# water_buzzer.net
KiCad netlist of a schematic drawn in EAGLE
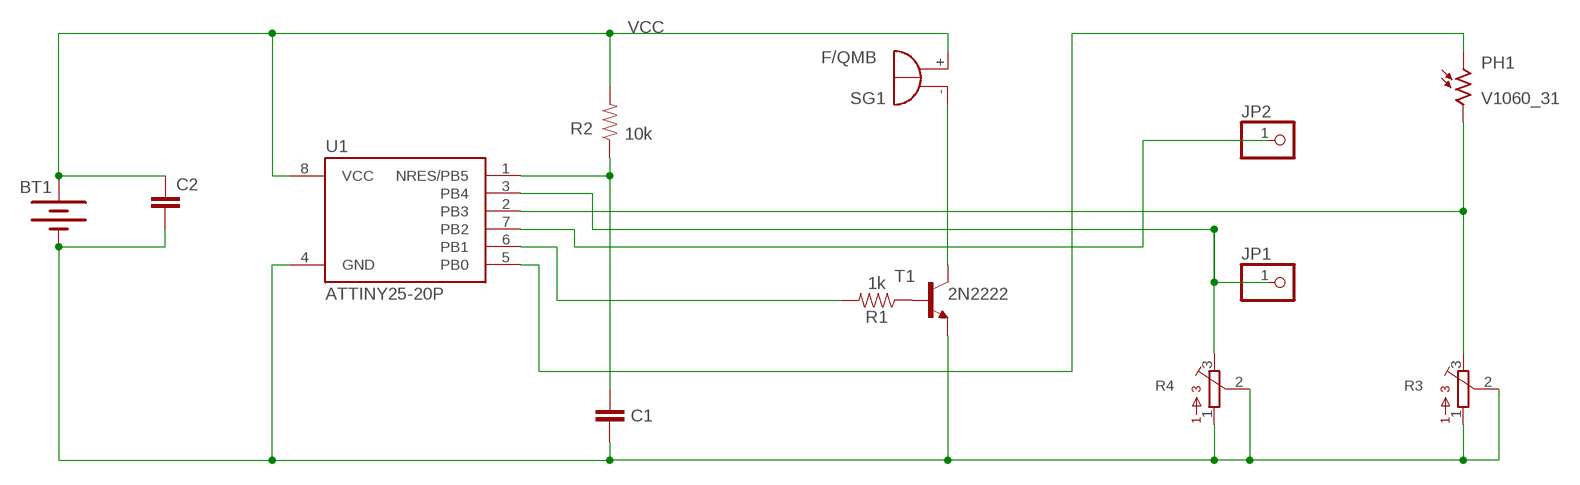
[diagram p0: schematic, sheet 1]

(export (version "E")
  (design (tool "Eeschema 10.0.6"))
  (components
    (comp (ref "BT1")
      (value "BATTERY-20MM_PTH")
      (footprint "eagle-import:BATTCOM_20MM_PTH")
      (libsource (lib "eagle-import") (part "BATTERY-20MM_PTH"))
    )
    (comp (ref "C1")
      (value "C5/2.5")
      (footprint "eagle-import:C5B2.5")
      (libsource (lib "eagle-import") (part "C5/2.5"))
    )
    (comp (ref "C2")
      (value "C5/2.5")
      (footprint "eagle-import:C5B2.5")
      (libsource (lib "eagle-import") (part "C5/2.5"))
    )
    (comp (ref "JP1")
      (value "PINHD-1X1")
      (footprint "eagle-import:1X01")
      (libsource (lib "eagle-import") (part "PINHD-1X1"))
    )
    (comp (ref "JP2")
      (value "PINHD-1X1")
      (footprint "eagle-import:1X01")
      (libsource (lib "eagle-import") (part "PINHD-1X1"))
    )
    (comp (ref "PH1")
      (value "V1060_31")
      (footprint "eagle-import:TO-5_V10")
      (libsource (lib "eagle-import") (part "?1060V_31"))
    )
    (comp (ref "R1")
      (value "1k")
      (footprint "eagle-import:AXIAL-0.3")
      (libsource (lib "eagle-import") (part "1KOHM-HORIZ-1/4W-5%"))
    )
    (comp (ref "R2")
      (value "10k")
      (footprint "eagle-import:AXIAL-0.3")
      (libsource (lib "eagle-import") (part "10KOHM-HORIZ-1/4W-5%"))
    )
    (comp (ref "R3")
      (value "3362R")
      (footprint "eagle-import:3362R")
      (libsource (lib "eagle-import") (part "3362R"))
    )
    (comp (ref "R4")
      (value "3362R")
      (footprint "eagle-import:3362R")
      (libsource (lib "eagle-import") (part "3362R"))
    )
    (comp (ref "SG1")
      (value "F/QMB")
      (footprint "eagle-import:F_QMB")
      (libsource (lib "eagle-import") (part "F/QMB"))
    )
    (comp (ref "T1")
      (value "2N2222")
      (footprint "eagle-import:TO92-EBC-OVAL")
      (libsource (lib "eagle-import") (part "2N2222"))
    )
    (comp (ref "U1")
      (value "ATTINY25-20P")
      (footprint "eagle-import:PDIP08_300MIL")
      (libsource (lib "eagle-import") (part "ATTINY25P-20"))
    )
  )
  (nets
    (net (code "1") (name "/VCC") (class "Default")
      (node (ref "BT1") (pin "1") (pinfunction "+_1") (pintype "power_in"))
      (node (ref "C2") (pin "1") (pinfunction "1_1") (pintype "passive"))
      (node (ref "R2") (pin "P$2") (pinfunction "2_P$2") (pintype "passive"))
      (node (ref "SG1") (pin "+") (pinfunction "-_+") (pintype "passive"))
      (node (ref "U1") (pin "8") (pinfunction "VCC_8") (pintype "power_in"))
    )
    (net (code "2") (name "Net-(BT1--)") (class "Default")
      (node (ref "BT1") (pin "2") (pinfunction "-_2") (pintype "power_in"))
      (node (ref "C1") (pin "1") (pinfunction "1_1") (pintype "passive"))
      (node (ref "C2") (pin "2") (pinfunction "2_2") (pintype "passive"))
      (node (ref "R3") (pin "1") (pinfunction "1_1") (pintype "passive"))
      (node (ref "R3") (pin "2") (pinfunction "2_2") (pintype "passive"))
      (node (ref "R4") (pin "1") (pinfunction "1_1") (pintype "passive"))
      (node (ref "R4") (pin "2") (pinfunction "2_2") (pintype "passive"))
      (node (ref "T1") (pin "E") (pinfunction "E_E") (pintype "passive"))
      (node (ref "U1") (pin "4") (pinfunction "GND_4") (pintype "power_in"))
    )
    (net (code "3") (name "Net-(R1-1)") (class "Default")
      (node (ref "R1") (pin "P$1") (pinfunction "1_P$1") (pintype "passive"))
      (node (ref "T1") (pin "B") (pinfunction "B_B") (pintype "passive"))
    )
    (net (code "4") (name "Net-(R1-2)") (class "Default")
      (node (ref "R1") (pin "P$2") (pinfunction "2_P$2") (pintype "passive"))
      (node (ref "U1") (pin "6") (pinfunction "PB1_6") (pintype "bidirectional"))
    )
    (net (code "5") (name "Net-(R2-1)") (class "Default")
      (node (ref "C1") (pin "2") (pinfunction "2_2") (pintype "passive"))
      (node (ref "R2") (pin "P$1") (pinfunction "1_P$1") (pintype "passive"))
      (node (ref "U1") (pin "1") (pinfunction "NRES/PB5_1") (pintype "bidirectional"))
    )
    (net (code "6") (name "Net-(SG1-+)") (class "Default")
      (node (ref "SG1") (pin "-") (pinfunction "+_-") (pintype "passive"))
      (node (ref "T1") (pin "C") (pinfunction "C_C") (pintype "passive"))
    )
    (net (code "7") (name "Net-(U1-PB0)") (class "Default")
      (node (ref "PH1") (pin "1") (pinfunction "1_1") (pintype "passive"))
      (node (ref "U1") (pin "5") (pinfunction "PB0_5") (pintype "bidirectional"))
    )
    (net (code "8") (name "Net-(U1-PB2)") (class "Default")
      (node (ref "JP2") (pin "1") (pinfunction "1_1") (pintype "passive"))
      (node (ref "U1") (pin "7") (pinfunction "PB2_7") (pintype "bidirectional"))
    )
    (net (code "9") (name "Net-(U1-PB3)") (class "Default")
      (node (ref "PH1") (pin "2") (pinfunction "2_2") (pintype "passive"))
      (node (ref "R3") (pin "3") (pinfunction "3_3") (pintype "passive"))
      (node (ref "U1") (pin "2") (pinfunction "PB3_2") (pintype "bidirectional"))
    )
    (net (code "10") (name "Net-(U1-PB4)") (class "Default")
      (node (ref "JP1") (pin "1") (pinfunction "1_1") (pintype "passive"))
      (node (ref "R4") (pin "3") (pinfunction "3_3") (pintype "passive"))
      (node (ref "U1") (pin "3") (pinfunction "PB4_3") (pintype "bidirectional"))
    )
  )
)
